# display.net
KiCad netlist of a schematic drawn in EAGLE
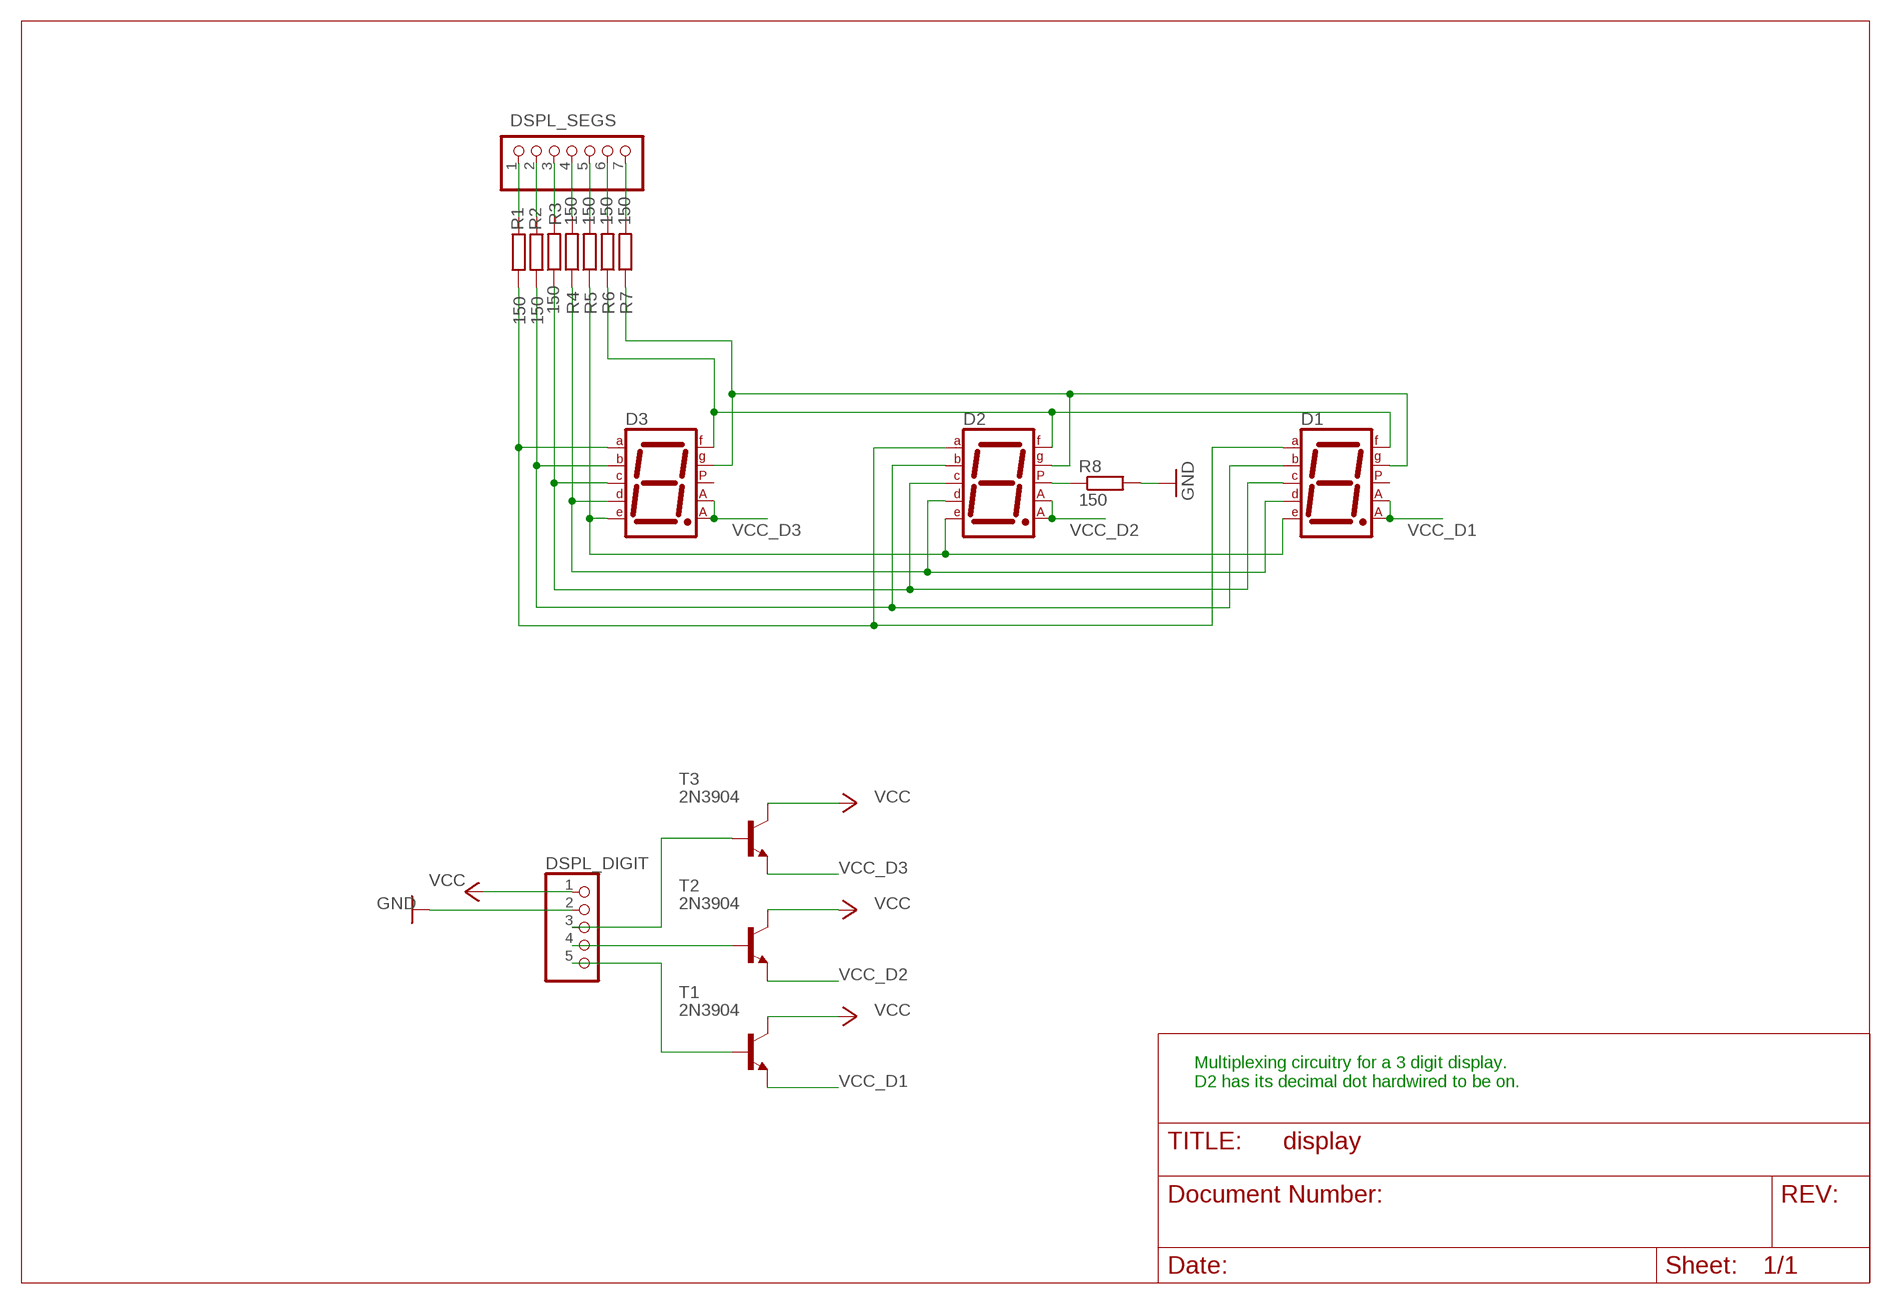
[diagram p0: schematic, sheet 1]

(export (version "E")
  (design (tool "Eeschema 10.0.6"))
  (components
    (comp (ref "D1")
      (value "7SEG-CA")
      (footprint "eagle-import:7SEG-13")
      (libsource (lib "eagle-import") (part "7SEG-CA"))
    )
    (comp (ref "D2")
      (value "7SEG-CA")
      (footprint "eagle-import:7SEG-13")
      (libsource (lib "eagle-import") (part "7SEG-CA"))
    )
    (comp (ref "D3")
      (value "7SEG-CA")
      (footprint "eagle-import:7SEG-13")
      (libsource (lib "eagle-import") (part "7SEG-CA"))
    )
    (comp (ref "DSPL_DIGIT")
      (value "PINHD-1X5")
      (footprint "eagle-import:1X05")
      (libsource (lib "eagle-import") (part "PINHD-1X5"))
    )
    (comp (ref "DSPL_SEGS")
      (value "PINHD-1X7")
      (footprint "eagle-import:1X07")
      (libsource (lib "eagle-import") (part "PINHD-1X7"))
    )
    (comp (ref "R1")
      (value "150")
      (footprint "eagle-import:0204_7")
      (libsource (lib "eagle-import") (part "R-EU_0204/7"))
    )
    (comp (ref "R2")
      (value "150")
      (footprint "eagle-import:0204_7")
      (libsource (lib "eagle-import") (part "R-EU_0204/7"))
    )
    (comp (ref "R3")
      (value "150")
      (footprint "eagle-import:0204_7")
      (libsource (lib "eagle-import") (part "R-EU_0204/7"))
    )
    (comp (ref "R4")
      (value "150")
      (footprint "eagle-import:0204_7")
      (libsource (lib "eagle-import") (part "R-EU_0204/7"))
    )
    (comp (ref "R5")
      (value "150")
      (footprint "eagle-import:0204_7")
      (libsource (lib "eagle-import") (part "R-EU_0204/7"))
    )
    (comp (ref "R6")
      (value "150")
      (footprint "eagle-import:0204_7")
      (libsource (lib "eagle-import") (part "R-EU_0204/7"))
    )
    (comp (ref "R7")
      (value "150")
      (footprint "eagle-import:0204_7")
      (libsource (lib "eagle-import") (part "R-EU_0204/7"))
    )
    (comp (ref "R8")
      (value "150")
      (footprint "eagle-import:0204_7")
      (libsource (lib "eagle-import") (part "R-EU_0204/7"))
    )
    (comp (ref "T1")
      (value "2N3904")
      (footprint "eagle-import:TO92")
      (libsource (lib "eagle-import") (part "2N3904"))
    )
    (comp (ref "T2")
      (value "2N3904")
      (footprint "eagle-import:TO92")
      (libsource (lib "eagle-import") (part "2N3904"))
    )
    (comp (ref "T3")
      (value "2N3904")
      (footprint "eagle-import:TO92")
      (libsource (lib "eagle-import") (part "2N3904"))
    )
  )
  (nets
    (net (code "1") (name "/VCC_D1") (class "Default")
      (node (ref "D1") (pin "3") (pinfunction "CA1_3") (pintype "passive"))
      (node (ref "D1") (pin "8") (pinfunction "CA2_8") (pintype "passive"))
      (node (ref "T1") (pin "3") (pinfunction "E_3") (pintype "passive"))
    )
    (net (code "2") (name "/VCC_D2") (class "Default")
      (node (ref "D2") (pin "3") (pinfunction "CA1_3") (pintype "passive"))
      (node (ref "D2") (pin "8") (pinfunction "CA2_8") (pintype "passive"))
      (node (ref "T2") (pin "3") (pinfunction "E_3") (pintype "passive"))
    )
    (net (code "3") (name "/VCC_D3") (class "Default")
      (node (ref "D3") (pin "3") (pinfunction "CA1_3") (pintype "passive"))
      (node (ref "D3") (pin "8") (pinfunction "CA2_8") (pintype "passive"))
      (node (ref "T3") (pin "3") (pinfunction "E_3") (pintype "passive"))
    )
    (net (code "4") (name "GND") (class "Default")
      (node (ref "DSPL_DIGIT") (pin "2") (pinfunction "2_2") (pintype "passive"))
      (node (ref "R8") (pin "2") (pinfunction "2_2") (pintype "passive"))
    )
    (net (code "5") (name "Net-(D1-A)") (class "Default")
      (node (ref "D1") (pin "7") (pinfunction "A_7") (pintype "passive"))
      (node (ref "D2") (pin "7") (pinfunction "A_7") (pintype "passive"))
      (node (ref "D3") (pin "7") (pinfunction "A_7") (pintype "passive"))
      (node (ref "R1") (pin "2") (pinfunction "2_2") (pintype "passive"))
    )
    (net (code "6") (name "Net-(D1-B)") (class "Default")
      (node (ref "D1") (pin "6") (pinfunction "B_6") (pintype "passive"))
      (node (ref "D2") (pin "6") (pinfunction "B_6") (pintype "passive"))
      (node (ref "D3") (pin "6") (pinfunction "B_6") (pintype "passive"))
      (node (ref "R2") (pin "2") (pinfunction "2_2") (pintype "passive"))
    )
    (net (code "7") (name "Net-(D1-C)") (class "Default")
      (node (ref "D1") (pin "4") (pinfunction "C_4") (pintype "passive"))
      (node (ref "D2") (pin "4") (pinfunction "C_4") (pintype "passive"))
      (node (ref "D3") (pin "4") (pinfunction "C_4") (pintype "passive"))
      (node (ref "R3") (pin "1") (pinfunction "1_1") (pintype "passive"))
    )
    (net (code "8") (name "Net-(D1-D)") (class "Default")
      (node (ref "D1") (pin "2") (pinfunction "D_2") (pintype "passive"))
      (node (ref "D2") (pin "2") (pinfunction "D_2") (pintype "passive"))
      (node (ref "D3") (pin "2") (pinfunction "D_2") (pintype "passive"))
      (node (ref "R4") (pin "1") (pinfunction "1_1") (pintype "passive"))
    )
    (net (code "9") (name "Net-(D1-E)") (class "Default")
      (node (ref "D1") (pin "1") (pinfunction "E_1") (pintype "passive"))
      (node (ref "D2") (pin "1") (pinfunction "E_1") (pintype "passive"))
      (node (ref "D3") (pin "1") (pinfunction "E_1") (pintype "passive"))
      (node (ref "R5") (pin "1") (pinfunction "1_1") (pintype "passive"))
    )
    (net (code "10") (name "Net-(D1-F)") (class "Default")
      (node (ref "D1") (pin "9") (pinfunction "F_9") (pintype "passive"))
      (node (ref "D2") (pin "9") (pinfunction "F_9") (pintype "passive"))
      (node (ref "D3") (pin "9") (pinfunction "F_9") (pintype "passive"))
      (node (ref "R6") (pin "1") (pinfunction "1_1") (pintype "passive"))
    )
    (net (code "11") (name "Net-(D1-G)") (class "Default")
      (node (ref "D1") (pin "10") (pinfunction "G_10") (pintype "passive"))
      (node (ref "D2") (pin "10") (pinfunction "G_10") (pintype "passive"))
      (node (ref "D3") (pin "10") (pinfunction "G_10") (pintype "passive"))
      (node (ref "R7") (pin "1") (pinfunction "1_1") (pintype "passive"))
    )
    (net (code "12") (name "Net-(D2-DP)") (class "Default")
      (node (ref "D2") (pin "5") (pinfunction "DP_5") (pintype "passive"))
      (node (ref "R8") (pin "1") (pinfunction "1_1") (pintype "passive"))
    )
    (net (code "13") (name "Net-(DSPL_SEGS-Pad1)") (class "Default")
      (node (ref "DSPL_SEGS") (pin "1") (pinfunction "1_1") (pintype "passive"))
      (node (ref "R1") (pin "1") (pinfunction "1_1") (pintype "passive"))
    )
    (net (code "14") (name "Net-(DSPL_SEGS-Pad2)") (class "Default")
      (node (ref "DSPL_SEGS") (pin "2") (pinfunction "2_2") (pintype "passive"))
      (node (ref "R2") (pin "1") (pinfunction "1_1") (pintype "passive"))
    )
    (net (code "15") (name "Net-(DSPL_SEGS-Pad3)") (class "Default")
      (node (ref "DSPL_SEGS") (pin "3") (pinfunction "3_3") (pintype "passive"))
      (node (ref "R3") (pin "2") (pinfunction "2_2") (pintype "passive"))
    )
    (net (code "16") (name "Net-(DSPL_SEGS-Pad4)") (class "Default")
      (node (ref "DSPL_SEGS") (pin "4") (pinfunction "4_4") (pintype "passive"))
      (node (ref "R4") (pin "2") (pinfunction "2_2") (pintype "passive"))
    )
    (net (code "17") (name "Net-(DSPL_SEGS-Pad5)") (class "Default")
      (node (ref "DSPL_SEGS") (pin "5") (pinfunction "5_5") (pintype "passive"))
      (node (ref "R5") (pin "2") (pinfunction "2_2") (pintype "passive"))
    )
    (net (code "18") (name "Net-(DSPL_SEGS-Pad6)") (class "Default")
      (node (ref "DSPL_SEGS") (pin "6") (pinfunction "6_6") (pintype "passive"))
      (node (ref "R6") (pin "2") (pinfunction "2_2") (pintype "passive"))
    )
    (net (code "19") (name "Net-(DSPL_SEGS-Pad7)") (class "Default")
      (node (ref "DSPL_SEGS") (pin "7") (pinfunction "7_7") (pintype "passive"))
      (node (ref "R7") (pin "2") (pinfunction "2_2") (pintype "passive"))
    )
    (net (code "20") (name "Net-(T1-B)") (class "Default")
      (node (ref "DSPL_DIGIT") (pin "5") (pinfunction "5_5") (pintype "passive"))
      (node (ref "T1") (pin "2") (pinfunction "B_2") (pintype "passive"))
    )
    (net (code "21") (name "Net-(T2-B)") (class "Default")
      (node (ref "DSPL_DIGIT") (pin "4") (pinfunction "4_4") (pintype "passive"))
      (node (ref "T2") (pin "2") (pinfunction "B_2") (pintype "passive"))
    )
    (net (code "22") (name "Net-(T3-B)") (class "Default")
      (node (ref "DSPL_DIGIT") (pin "3") (pinfunction "3_3") (pintype "passive"))
      (node (ref "T3") (pin "2") (pinfunction "B_2") (pintype "passive"))
    )
    (net (code "23") (name "VCC") (class "Default")
      (node (ref "DSPL_DIGIT") (pin "1") (pinfunction "1_1") (pintype "passive"))
      (node (ref "T1") (pin "1") (pinfunction "C_1") (pintype "passive"))
      (node (ref "T2") (pin "1") (pinfunction "C_1") (pintype "passive"))
      (node (ref "T3") (pin "1") (pinfunction "C_1") (pintype "passive"))
    )
    (net (code "24") (name "unconnected-(D1-DP-Pad5)") (class "Default")
      (node (ref "D1") (pin "5") (pinfunction "DP_5") (pintype "passive"))
    )
    (net (code "25") (name "unconnected-(D3-DP-Pad5)") (class "Default")
      (node (ref "D3") (pin "5") (pinfunction "DP_5") (pintype "passive"))
    )
  )
)
